# 3_IO.net
KiCad netlist of a schematic drawn in Altium Designer
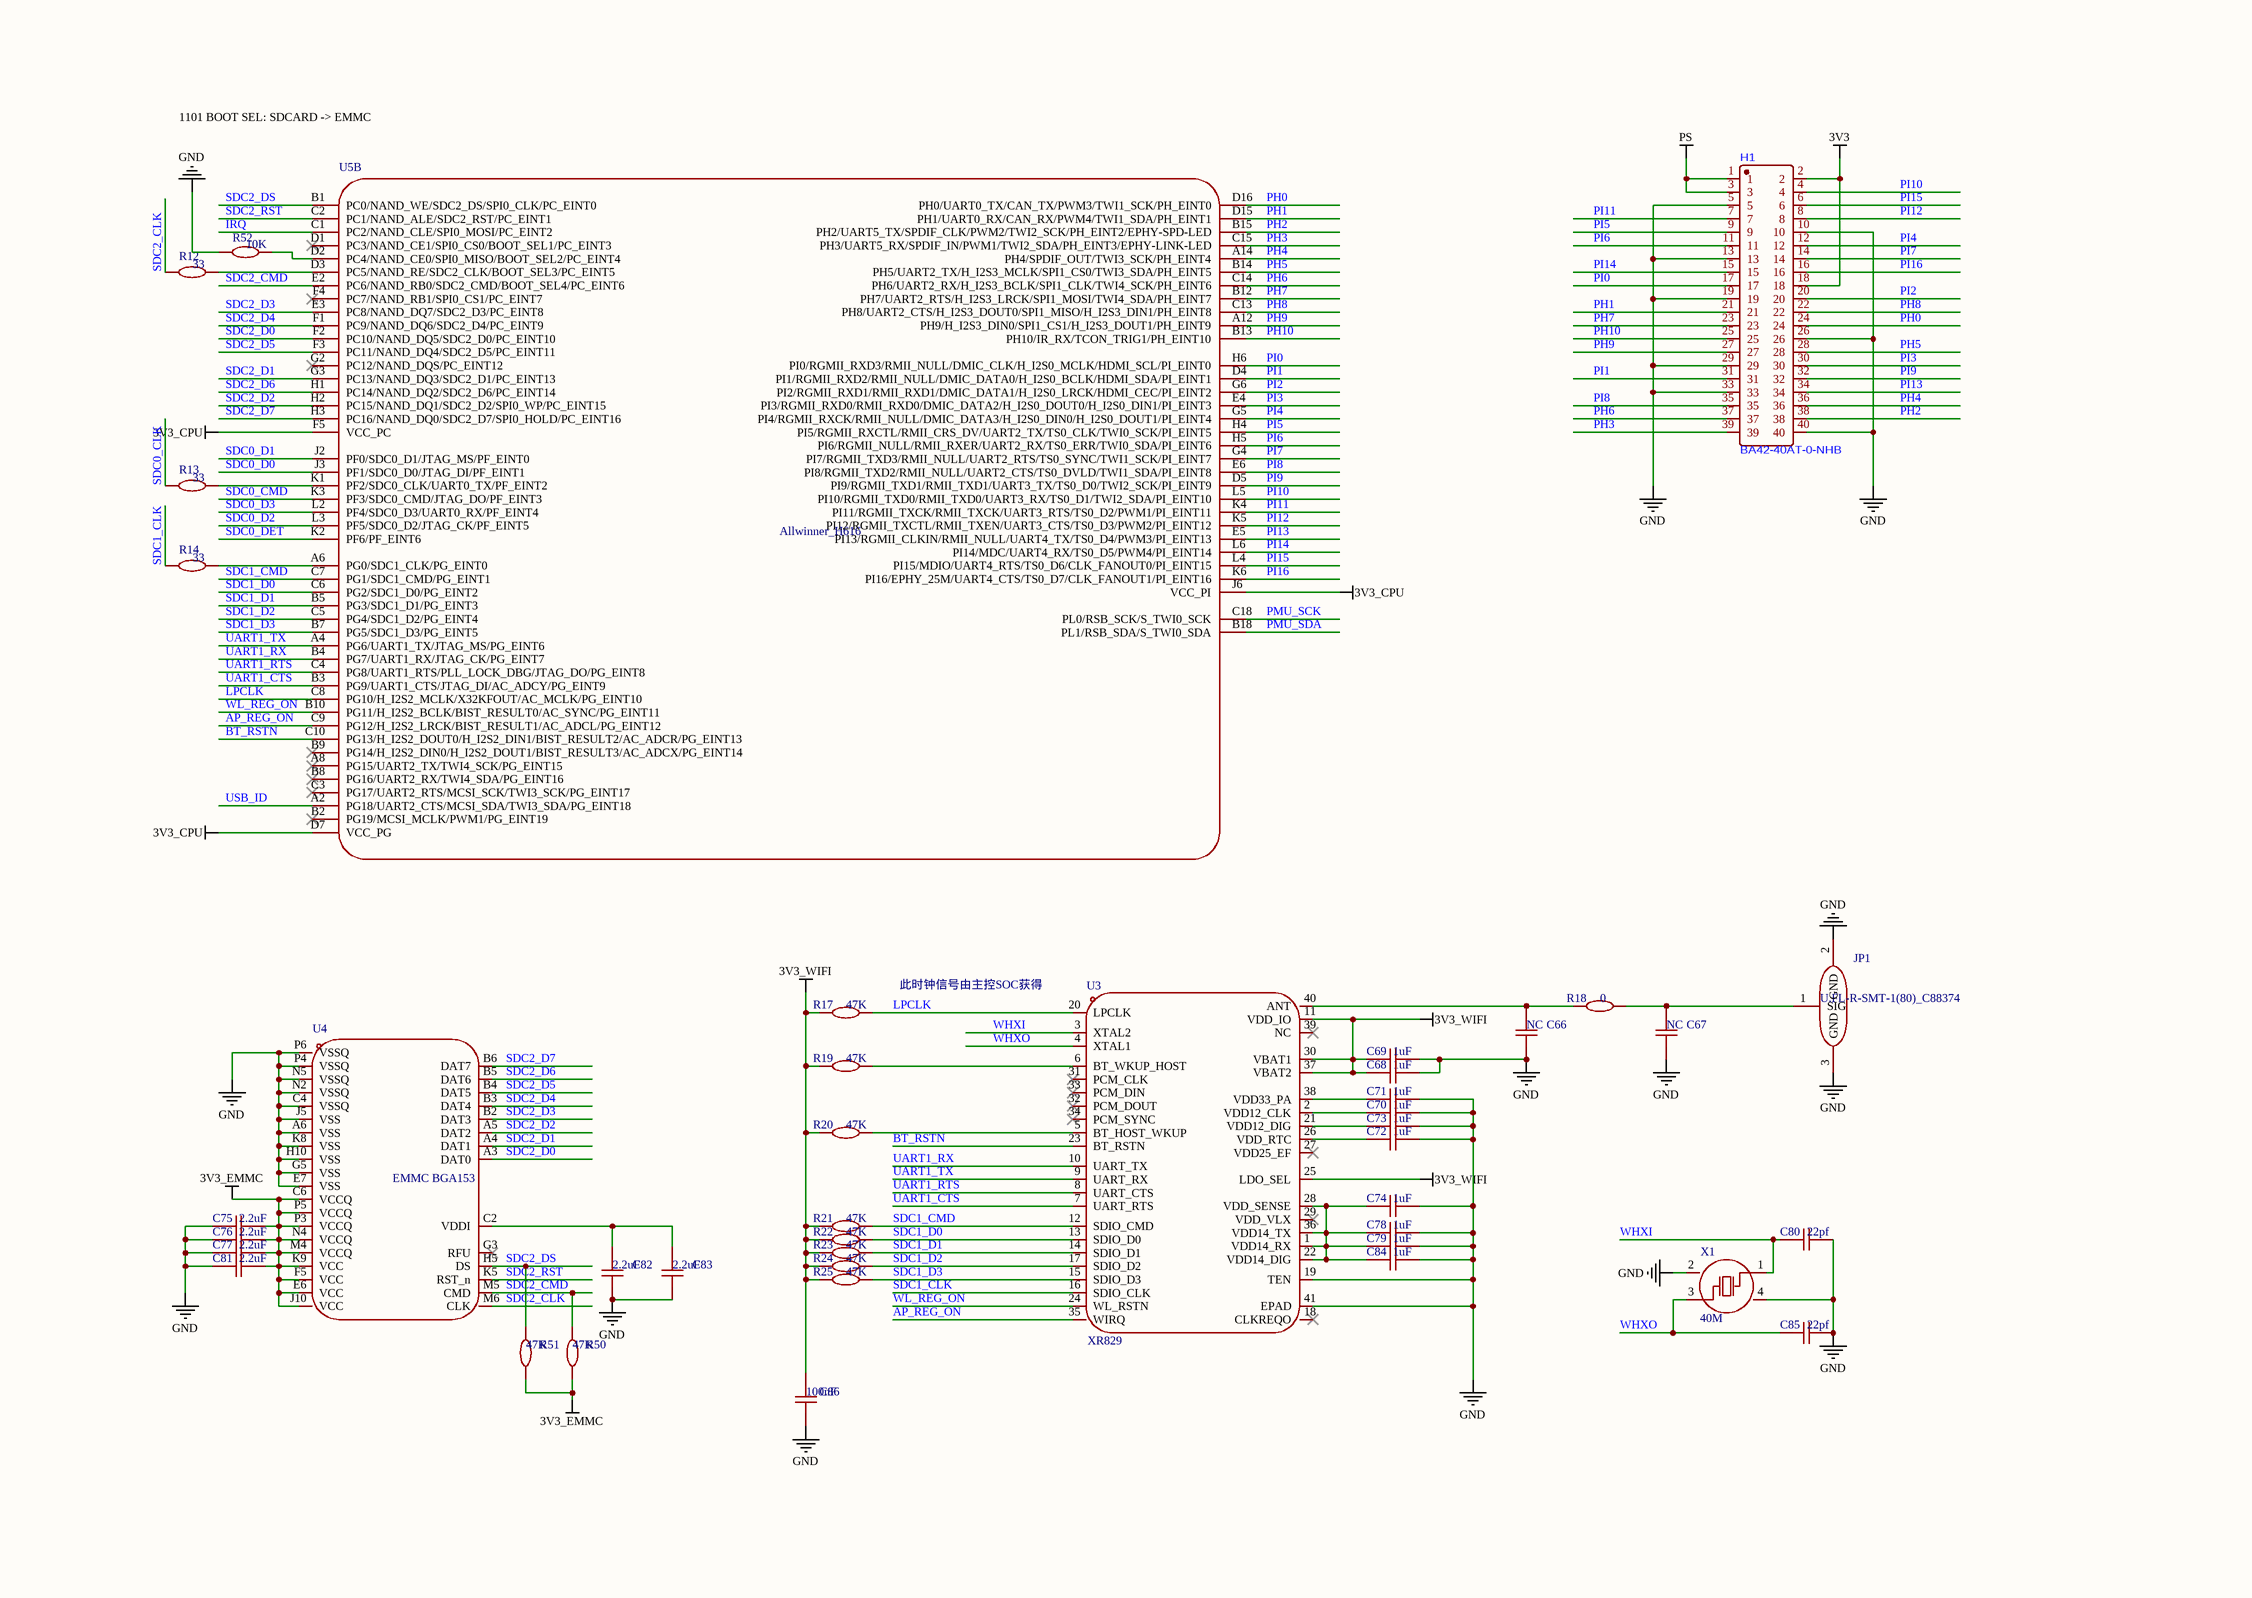
[diagram p0: 3_IO.schdoc]

(export (version "E")
  (design (tool "Eeschema 10.0.6"))
  (components
    (comp (ref "C66") (value "NC") (footprint "PCB:C0402") (libsource (lib "PCB_Project") (part "CAP_0402")))
    (comp (ref "C67") (value "NC") (footprint "PCB:C0402") (libsource (lib "PCB_Project") (part "CAP_0402")))
    (comp (ref "C68") (value "1uF") (footprint "PCB:C0402") (libsource (lib "PCB_Project") (part "CAP_0402")))
    (comp (ref "C69") (value "1uF") (footprint "PCB:C0402") (libsource (lib "PCB_Project") (part "CAP_0402")))
    (comp (ref "C70") (value "1uF") (footprint "PCB:C0402") (libsource (lib "PCB_Project") (part "CAP_0402")))
    (comp (ref "C71") (value "1uF") (footprint "PCB:C0402") (libsource (lib "PCB_Project") (part "CAP_0402")))
    (comp (ref "C72") (value "1uF") (footprint "PCB:C0402") (libsource (lib "PCB_Project") (part "CAP_0402")))
    (comp (ref "C73") (value "1uF") (footprint "PCB:C0402") (libsource (lib "PCB_Project") (part "CAP_0402")))
    (comp (ref "C74") (value "1uF") (footprint "PCB:C0402") (libsource (lib "PCB_Project") (part "CAP_0402")))
    (comp (ref "C75")
      (value "2.2uF")
      (footprint "PCB:C0402")
      (libsource (lib "PCB_Project") (part "CAP_0402"))
    )
    (comp (ref "C76")
      (value "2.2uF")
      (footprint "PCB:C0402")
      (libsource (lib "PCB_Project") (part "CAP_0402"))
    )
    (comp (ref "C77")
      (value "2.2uF")
      (footprint "PCB:C0402")
      (libsource (lib "PCB_Project") (part "CAP_0402"))
    )
    (comp (ref "C78") (value "1uF") (footprint "PCB:C0402") (libsource (lib "PCB_Project") (part "CAP_0402")))
    (comp (ref "C79") (value "1uF") (footprint "PCB:C0402") (libsource (lib "PCB_Project") (part "CAP_0402")))
    (comp (ref "C80")
      (value "22pf")
      (footprint "PCB:C0402")
      (libsource (lib "PCB_Project") (part "CAP_0402"))
    )
    (comp (ref "C81")
      (value "2.2uF")
      (footprint "PCB:C0402")
      (libsource (lib "PCB_Project") (part "CAP_0402"))
    )
    (comp (ref "C82")
      (value "2.2uF")
      (footprint "PCB:C0402")
      (libsource (lib "PCB_Project") (part "CAP_0402"))
    )
    (comp (ref "C83")
      (value "2.2uF")
      (footprint "PCB:C0402")
      (libsource (lib "PCB_Project") (part "CAP_0402"))
    )
    (comp (ref "C84") (value "1uF") (footprint "PCB:C0402") (libsource (lib "PCB_Project") (part "CAP_0402")))
    (comp (ref "C85")
      (value "22pf")
      (footprint "PCB:C0402")
      (libsource (lib "PCB_Project") (part "CAP_0402"))
    )
    (comp (ref "C86")
      (value "100nF")
      (footprint "PCB:c0402-nsk_1")
      (libsource (lib "PCB_Project") (part "FN15X104K250PNG"))
    )
    (comp (ref "H1")
      (value "BA42-40AT-0-NHB")
      (footprint "PCB:CONN-SMD_40P-P0.80_10144517-042802LF")
      (libsource (lib "PCB_Project") (part "BA42-40AT-0-NHB"))
    )
    (comp (ref "JP1")
      (value "U.FL-R-SMT-1(80)_C88374")
      (footprint "PCB:RF-SMD_FRF05002-JSS103M")
      (libsource (lib "PCB_Project") (part "U.FL-R-SMT-1(80)_C88374"))
    )
    (comp (ref "R12")
      (value "33")
      (footprint "PCB:R0402-NSK_2")
      (libsource (lib "PCB_Project") (part "Res_0402"))
    )
    (comp (ref "R13")
      (value "33")
      (footprint "PCB:R0402-NSK_2")
      (libsource (lib "PCB_Project") (part "Res_0402"))
    )
    (comp (ref "R14")
      (value "33")
      (footprint "PCB:R0402-NSK_2")
      (libsource (lib "PCB_Project") (part "Res_0402"))
    )
    (comp (ref "R17")
      (value "47K")
      (footprint "PCB:R0402-NSK_2")
      (libsource (lib "PCB_Project") (part "Res_0402"))
    )
    (comp (ref "R18")
      (value "0")
      (footprint "PCB:R0402-NSK_2")
      (libsource (lib "PCB_Project") (part "Res_0402"))
    )
    (comp (ref "R19")
      (value "47K")
      (footprint "PCB:R0402-NSK_2")
      (libsource (lib "PCB_Project") (part "Res_0402"))
    )
    (comp (ref "R20")
      (value "47K")
      (footprint "PCB:R0402-NSK_2")
      (libsource (lib "PCB_Project") (part "Res_0402"))
    )
    (comp (ref "R21")
      (value "47K")
      (footprint "PCB:R0402-NSK_2")
      (libsource (lib "PCB_Project") (part "Res_0402"))
    )
    (comp (ref "R22")
      (value "47K")
      (footprint "PCB:R0402-NSK_2")
      (libsource (lib "PCB_Project") (part "Res_0402"))
    )
    (comp (ref "R23")
      (value "47K")
      (footprint "PCB:R0402-NSK_2")
      (libsource (lib "PCB_Project") (part "Res_0402"))
    )
    (comp (ref "R24")
      (value "47K")
      (footprint "PCB:R0402-NSK_2")
      (libsource (lib "PCB_Project") (part "Res_0402"))
    )
    (comp (ref "R25")
      (value "47K")
      (footprint "PCB:R0402-NSK_2")
      (libsource (lib "PCB_Project") (part "Res_0402"))
    )
    (comp (ref "R50")
      (value "47K")
      (footprint "PCB:R0402-NSK_2")
      (libsource (lib "PCB_Project") (part "Res_0402"))
    )
    (comp (ref "R51")
      (value "47K")
      (footprint "PCB:R0402-NSK_2")
      (libsource (lib "PCB_Project") (part "Res_0402"))
    )
    (comp (ref "R52")
      (value "10K")
      (footprint "PCB:R0402-NSK_2")
      (libsource (lib "PCB_Project") (part "Res_0402"))
    )
    (comp (ref "U3")
      (value "XR829")
      (footprint "PCB:QFN-40_L5.0-W5.0-P0.40-BL-EP3.4")
      (libsource (lib "PCB_Project") (part "XR829"))
    )
    (comp (ref "U4")
      (value "EMMC BGA153")
      (footprint "PCB:FBGA-153_L13.0-W11.5")
      (libsource (lib "PCB_Project") (part "EMMC BGA153"))
    )
    (comp (ref "U5")
      (value "Allwinner_H616")
      (footprint "PCB:BGA284P65B1200_1400H125")
      (libsource (lib "PCB_Project") (part "Allwinner_H616"))
    )
    (comp (ref "X1")
      (value "40M")
      (footprint "PCB:OSC-SMD_4P-L2.0-W1.6-BL")
      (libsource (lib "PCB_Project") (part "SX32Y024000BC1T"))
    )
  )
  (nets
    (net (code "1") (name "/AP_REG_ON") (class "Default")
      (node (ref "U3") (pin "35") (pinfunction "WIRQ_35") (pintype "passive"))
      (node (ref "U5") (pin "C9") (pinfunction "PG12/H_I2S2_LRCK/BIST_RESULT1/AC_ADCL/PG_EINT12_C9") (pintype "passive"))
    )
    (net (code "2") (name "/BT_RSTN") (class "Default")
      (node (ref "U3") (pin "23") (pinfunction "BT_RSTN_23") (pintype "passive"))
      (node (ref "U5") (pin "C10") (pinfunction "PG13/H_I2S2_DOUT0/H_I2S2_DIN1/BIST_RESULT2/AC_ADCR/PG_EINT13_C10") (pintype "passive"))
    )
    (net (code "3") (name "/IRQ") (class "Default")
      (node (ref "U5") (pin "C1") (pinfunction "PC2/NAND_CLE/SPI0_MOSI/PC_EINT2_C1") (pintype "passive"))
    )
    (net (code "4") (name "/LPCLK") (class "Default")
      (node (ref "R17") (pin "2") (pinfunction "2_2") (pintype "passive"))
      (node (ref "U3") (pin "20") (pinfunction "LPCLK_20") (pintype "passive"))
      (node (ref "U5") (pin "C8") (pinfunction "PG10/H_I2S2_MCLK/X32KFOUT/AC_MCLK/PG_EINT10_C8") (pintype "passive"))
    )
    (net (code "5") (name "/PH0") (class "Default")
      (node (ref "H1") (pin "24") (pinfunction "24_24") (pintype "passive"))
      (node (ref "U5") (pin "D16") (pinfunction "PH0/UART0_TX/CAN_TX/PWM3/TWI1_SCK/PH_EINT0_D16") (pintype "passive"))
    )
    (net (code "6") (name "/PH1") (class "Default")
      (node (ref "H1") (pin "21") (pinfunction "21_21") (pintype "passive"))
      (node (ref "U5") (pin "D15") (pinfunction "PH1/UART0_RX/CAN_RX/PWM4/TWI1_SDA/PH_EINT1_D15") (pintype "passive"))
    )
    (net (code "7") (name "/PH2") (class "Default")
      (node (ref "H1") (pin "38") (pinfunction "38_38") (pintype "passive"))
      (node (ref "U5") (pin "B15") (pinfunction "PH2/UART5_TX/SPDIF_CLK/PWM2/TWI2_SCK/PH_EINT2/EPHY-SPD-LED_B15") (pintype "passive"))
    )
    (net (code "8") (name "/PH3") (class "Default")
      (node (ref "H1") (pin "39") (pinfunction "39_39") (pintype "passive"))
      (node (ref "U5") (pin "C15") (pinfunction "PH3/UART5_RX/SPDIF_IN/PWM1/TWI2_SDA/PH_EINT3/EPHY-LINK-LED_C15") (pintype "passive"))
    )
    (net (code "9") (name "/PH4") (class "Default")
      (node (ref "H1") (pin "36") (pinfunction "36_36") (pintype "passive"))
      (node (ref "U5") (pin "A14") (pinfunction "PH4/SPDIF_OUT/TWI3_SCK/PH_EINT4_A14") (pintype "passive"))
    )
    (net (code "10") (name "/PH5") (class "Default")
      (node (ref "H1") (pin "28") (pinfunction "28_28") (pintype "passive"))
      (node (ref "U5") (pin "B14") (pinfunction "PH5/UART2_TX/H_I2S3_MCLK/SPI1_CS0/TWI3_SDA/PH_EINT5_B14") (pintype "passive"))
    )
    (net (code "11") (name "/PH6") (class "Default")
      (node (ref "H1") (pin "37") (pinfunction "37_37") (pintype "passive"))
      (node (ref "U5") (pin "C14") (pinfunction "PH6/UART2_RX/H_I2S3_BCLK/SPI1_CLK/TWI4_SCK/PH_EINT6_C14") (pintype "passive"))
    )
    (net (code "12") (name "/PH7") (class "Default")
      (node (ref "H1") (pin "23") (pinfunction "23_23") (pintype "passive"))
      (node (ref "U5") (pin "B12") (pinfunction "PH7/UART2_RTS/H_I2S3_LRCK/SPI1_MOSI/TWI4_SDA/PH_EINT7_B12") (pintype "passive"))
    )
    (net (code "13") (name "/PH8") (class "Default")
      (node (ref "H1") (pin "22") (pinfunction "22_22") (pintype "passive"))
      (node (ref "U5") (pin "C13") (pinfunction "PH8/UART2_CTS/H_I2S3_DOUT0/SPI1_MISO/H_I2S3_DIN1/PH_EINT8_C13") (pintype "passive"))
    )
    (net (code "14") (name "/PH9") (class "Default")
      (node (ref "H1") (pin "27") (pinfunction "27_27") (pintype "passive"))
      (node (ref "U5") (pin "A12") (pinfunction "PH9/H_I2S3_DIN0/SPI1_CS1/H_I2S3_DOUT1/PH_EINT9_A12") (pintype "passive"))
    )
    (net (code "15") (name "/PH10") (class "Default")
      (node (ref "H1") (pin "25") (pinfunction "25_25") (pintype "passive"))
      (node (ref "U5") (pin "B13") (pinfunction "PH10/IR_RX/TCON_TRIG1/PH_EINT10_B13") (pintype "passive"))
    )
    (net (code "16") (name "/PI0") (class "Default")
      (node (ref "H1") (pin "17") (pinfunction "17_17") (pintype "passive"))
      (node (ref "U5") (pin "H6") (pinfunction "PI0/RGMII_RXD3/RMII_NULL/DMIC_CLK/H_I2S0_MCLK/HDMI_SCL/PI_EINT0_H6") (pintype "passive"))
    )
    (net (code "17") (name "/PI1") (class "Default")
      (node (ref "H1") (pin "31") (pinfunction "31_31") (pintype "passive"))
      (node (ref "U5") (pin "D4") (pinfunction "PI1/RGMII_RXD2/RMII_NULL/DMIC_DATA0/H_I2S0_BCLK/HDMI_SDA/PI_EINT1_D4") (pintype "passive"))
    )
    (net (code "18") (name "/PI2") (class "Default")
      (node (ref "H1") (pin "20") (pinfunction "20_20") (pintype "passive"))
      (node (ref "U5") (pin "G6") (pinfunction "PI2/RGMII_RXD1/RMII_RXD1/DMIC_DATA1/H_I2S0_LRCK/HDMI_CEC/PI_EINT2_G6") (pintype "passive"))
    )
    (net (code "19") (name "/PI3") (class "Default")
      (node (ref "H1") (pin "30") (pinfunction "30_30") (pintype "passive"))
      (node (ref "U5") (pin "E4") (pinfunction "PI3/RGMII_RXD0/RMII_RXD0/DMIC_DATA2/H_I2S0_DOUT0/H_I2S0_DIN1/PI_EINT3_E4") (pintype "passive"))
    )
    (net (code "20") (name "/PI4") (class "Default")
      (node (ref "H1") (pin "12") (pinfunction "12_12") (pintype "passive"))
      (node (ref "U5") (pin "G5") (pinfunction "PI4/RGMII_RXCK/RMII_NULL/DMIC_DATA3/H_I2S0_DIN0/H_I2S0_DOUT1/PI_EINT4_G5") (pintype "passive"))
    )
    (net (code "21") (name "/PI5") (class "Default")
      (node (ref "H1") (pin "9") (pinfunction "9_9") (pintype "passive"))
      (node (ref "U5") (pin "H4") (pinfunction "PI5/RGMII_RXCTL/RMII_CRS_DV/UART2_TX/TS0_CLK/TWI0_SCK/PI_EINT5_H4") (pintype "passive"))
    )
    (net (code "22") (name "/PI6") (class "Default")
      (node (ref "H1") (pin "11") (pinfunction "11_11") (pintype "passive"))
      (node (ref "U5") (pin "H5") (pinfunction "PI6/RGMII_NULL/RMII_RXER/UART2_RX/TS0_ERR/TWI0_SDA/PI_EINT6_H5") (pintype "passive"))
    )
    (net (code "23") (name "/PI7") (class "Default")
      (node (ref "H1") (pin "14") (pinfunction "14_14") (pintype "passive"))
      (node (ref "U5") (pin "G4") (pinfunction "PI7/RGMII_TXD3/RMII_NULL/UART2_RTS/TS0_SYNC/TWI1_SCK/PI_EINT7_G4") (pintype "passive"))
    )
    (net (code "24") (name "/PI8") (class "Default")
      (node (ref "H1") (pin "35") (pinfunction "35_35") (pintype "passive"))
      (node (ref "U5") (pin "E6") (pinfunction "PI8/RGMII_TXD2/RMII_NULL/UART2_CTS/TS0_DVLD/TWI1_SDA/PI_EINT8_E6") (pintype "passive"))
    )
    (net (code "25") (name "/PI9") (class "Default")
      (node (ref "H1") (pin "32") (pinfunction "32_32") (pintype "passive"))
      (node (ref "U5") (pin "D5") (pinfunction "PI9/RGMII_TXD1/RMII_TXD1/UART3_TX/TS0_D0/TWI2_SCK/PI_EINT9_D5") (pintype "passive"))
    )
    (net (code "26") (name "/PI10") (class "Default")
      (node (ref "H1") (pin "4") (pinfunction "4_4") (pintype "passive"))
      (node (ref "U5") (pin "L5") (pinfunction "PI10/RGMII_TXD0/RMII_TXD0/UART3_RX/TS0_D1/TWI2_SDA/PI_EINT10_L5") (pintype "passive"))
    )
    (net (code "27") (name "/PI11") (class "Default")
      (node (ref "H1") (pin "7") (pinfunction "7_7") (pintype "passive"))
      (node (ref "U5") (pin "K4") (pinfunction "PI11/RGMII_TXCK/RMII_TXCK/UART3_RTS/TS0_D2/PWM1/PI_EINT11_K4") (pintype "passive"))
    )
    (net (code "28") (name "/PI12") (class "Default")
      (node (ref "H1") (pin "8") (pinfunction "8_8") (pintype "passive"))
      (node (ref "U5") (pin "K5") (pinfunction "PI12/RGMII_TXCTL/RMII_TXEN/UART3_CTS/TS0_D3/PWM2/PI_EINT12_K5") (pintype "passive"))
    )
    (net (code "29") (name "/PI13") (class "Default")
      (node (ref "H1") (pin "34") (pinfunction "34_34") (pintype "passive"))
      (node (ref "U5") (pin "E5") (pinfunction "PI13/RGMII_CLKIN/RMII_NULL/UART4_TX/TS0_D4/PWM3/PI_EINT13_E5") (pintype "passive"))
    )
    (net (code "30") (name "/PI14") (class "Default")
      (node (ref "H1") (pin "15") (pinfunction "15_15") (pintype "passive"))
      (node (ref "U5") (pin "L6") (pinfunction "PI14/MDC/UART4_RX/TS0_D5/PWM4/PI_EINT14_L6") (pintype "passive"))
    )
    (net (code "31") (name "/PI15") (class "Default")
      (node (ref "H1") (pin "6") (pinfunction "6_6") (pintype "passive"))
      (node (ref "U5") (pin "L4") (pinfunction "PI15/MDIO/UART4_RTS/TS0_D6/CLK_FANOUT0/PI_EINT15_L4") (pintype "passive"))
    )
    (net (code "32") (name "/PI16") (class "Default")
      (node (ref "H1") (pin "16") (pinfunction "16_16") (pintype "passive"))
      (node (ref "U5") (pin "K6") (pinfunction "PI16/EPHY_25M/UART4_CTS/TS0_D7/CLK_FANOUT1/PI_EINT16_K6") (pintype "passive"))
    )
    (net (code "33") (name "/PMU_SCK") (class "Default")
      (node (ref "U5") (pin "C18") (pinfunction "PL0/RSB_SCK/S_TWI0_SCK_C18") (pintype "passive"))
    )
    (net (code "34") (name "/PMU_SDA") (class "Default")
      (node (ref "U5") (pin "B18") (pinfunction "PL1/RSB_SDA/S_TWI0_SDA_B18") (pintype "passive"))
    )
    (net (code "35") (name "/SDC0_CLK") (class "Default")
      (node (ref "R13") (pin "1") (pinfunction "1_1") (pintype "passive"))
    )
    (net (code "36") (name "/SDC0_CMD") (class "Default")
      (node (ref "U5") (pin "K3") (pinfunction "PF3/SDC0_CMD/JTAG_DO/PF_EINT3_K3") (pintype "passive"))
    )
    (net (code "37") (name "/SDC0_D0") (class "Default")
      (node (ref "U5") (pin "J3") (pinfunction "PF1/SDC0_D0/JTAG_DI/PF_EINT1_J3") (pintype "passive"))
    )
    (net (code "38") (name "/SDC0_D1") (class "Default")
      (node (ref "U5") (pin "J2") (pinfunction "PF0/SDC0_D1/JTAG_MS/PF_EINT0_J2") (pintype "passive"))
    )
    (net (code "39") (name "/SDC0_D2") (class "Default")
      (node (ref "U5") (pin "L3") (pinfunction "PF5/SDC0_D2/JTAG_CK/PF_EINT5_L3") (pintype "passive"))
    )
    (net (code "40") (name "/SDC0_D3") (class "Default")
      (node (ref "U5") (pin "L2") (pinfunction "PF4/SDC0_D3/UART0_RX/PF_EINT4_L2") (pintype "passive"))
    )
    (net (code "41") (name "/SDC0_DET") (class "Default")
      (node (ref "U5") (pin "K2") (pinfunction "PF6/PF_EINT6_K2") (pintype "passive"))
    )
    (net (code "42") (name "/SDC1_CLK") (class "Default")
      (node (ref "R14") (pin "1") (pinfunction "1_1") (pintype "passive"))
      (node (ref "U3") (pin "16") (pinfunction "SDIO_CLK_16") (pintype "passive"))
    )
    (net (code "43") (name "/SDC1_CMD") (class "Default")
      (node (ref "R21") (pin "2") (pinfunction "2_2") (pintype "passive"))
      (node (ref "U3") (pin "12") (pinfunction "SDIO_CMD_12") (pintype "passive"))
      (node (ref "U5") (pin "C7") (pinfunction "PG1/SDC1_CMD/PG_EINT1_C7") (pintype "passive"))
    )
    (net (code "44") (name "/SDC1_D0") (class "Default")
      (node (ref "R22") (pin "2") (pinfunction "2_2") (pintype "passive"))
      (node (ref "U3") (pin "13") (pinfunction "SDIO_D0_13") (pintype "passive"))
      (node (ref "U5") (pin "C6") (pinfunction "PG2/SDC1_D0/PG_EINT2_C6") (pintype "passive"))
    )
    (net (code "45") (name "/SDC1_D1") (class "Default")
      (node (ref "R23") (pin "2") (pinfunction "2_2") (pintype "passive"))
      (node (ref "U3") (pin "14") (pinfunction "SDIO_D1_14") (pintype "passive"))
      (node (ref "U5") (pin "B5") (pinfunction "PG3/SDC1_D1/PG_EINT3_B5") (pintype "passive"))
    )
    (net (code "46") (name "/SDC1_D2") (class "Default")
      (node (ref "R24") (pin "2") (pinfunction "2_2") (pintype "passive"))
      (node (ref "U3") (pin "17") (pinfunction "SDIO_D2_17") (pintype "passive"))
      (node (ref "U5") (pin "C5") (pinfunction "PG4/SDC1_D2/PG_EINT4_C5") (pintype "passive"))
    )
    (net (code "47") (name "/SDC1_D3") (class "Default")
      (node (ref "R25") (pin "2") (pinfunction "2_2") (pintype "passive"))
      (node (ref "U3") (pin "15") (pinfunction "SDIO_D3_15") (pintype "passive"))
      (node (ref "U5") (pin "B7") (pinfunction "PG5/SDC1_D3/PG_EINT5_B7") (pintype "passive"))
    )
    (net (code "48") (name "/SDC2_CLK") (class "Default")
      (node (ref "R12") (pin "1") (pinfunction "1_1") (pintype "passive"))
      (node (ref "U4") (pin "M6") (pinfunction "CLK_M6") (pintype "passive"))
    )
    (net (code "49") (name "/SDC2_CMD") (class "Default")
      (node (ref "R50") (pin "2") (pinfunction "2_2") (pintype "passive"))
      (node (ref "U4") (pin "M5") (pinfunction "CMD_M5") (pintype "passive"))
      (node (ref "U5") (pin "E2") (pinfunction "PC6/NAND_RB0/SDC2_CMD/BOOT_SEL4/PC_EINT6_E2") (pintype "passive"))
    )
    (net (code "50") (name "/SDC2_D0") (class "Default")
      (node (ref "U4") (pin "A3") (pinfunction "DAT0_A3") (pintype "passive"))
      (node (ref "U5") (pin "F2") (pinfunction "PC10/NAND_DQ5/SDC2_D0/PC_EINT10_F2") (pintype "passive"))
    )
    (net (code "51") (name "/SDC2_D1") (class "Default")
      (node (ref "U4") (pin "A4") (pinfunction "DAT1_A4") (pintype "passive"))
      (node (ref "U5") (pin "G3") (pinfunction "PC13/NAND_DQ3/SDC2_D1/PC_EINT13_G3") (pintype "passive"))
    )
    (net (code "52") (name "/SDC2_D2") (class "Default")
      (node (ref "U4") (pin "A5") (pinfunction "DAT2_A5") (pintype "passive"))
      (node (ref "U5") (pin "H2") (pinfunction "PC15/NAND_DQ1/SDC2_D2/SPI0_WP/PC_EINT15_H2") (pintype "passive"))
    )
    (net (code "53") (name "/SDC2_D3") (class "Default")
      (node (ref "U4") (pin "B2") (pinfunction "DAT3_B2") (pintype "passive"))
      (node (ref "U5") (pin "E3") (pinfunction "PC8/NAND_DQ7/SDC2_D3/PC_EINT8_E3") (pintype "passive"))
    )
    (net (code "54") (name "/SDC2_D4") (class "Default")
      (node (ref "U4") (pin "B3") (pinfunction "DAT4_B3") (pintype "passive"))
      (node (ref "U5") (pin "F1") (pinfunction "PC9/NAND_DQ6/SDC2_D4/PC_EINT9_F1") (pintype "passive"))
    )
    (net (code "55") (name "/SDC2_D5") (class "Default")
      (node (ref "U4") (pin "B4") (pinfunction "DAT5_B4") (pintype "passive"))
      (node (ref "U5") (pin "F3") (pinfunction "PC11/NAND_DQ4/SDC2_D5/PC_EINT11_F3") (pintype "passive"))
    )
    (net (code "56") (name "/SDC2_D6") (class "Default")
      (node (ref "U4") (pin "B5") (pinfunction "DAT6_B5") (pintype "passive"))
      (node (ref "U5") (pin "H1") (pinfunction "PC14/NAND_DQ2/SDC2_D6/PC_EINT14_H1") (pintype "passive"))
    )
    (net (code "57") (name "/SDC2_D7") (class "Default")
      (node (ref "U4") (pin "B6") (pinfunction "DAT7_B6") (pintype "passive"))
      (node (ref "U5") (pin "H3") (pinfunction "PC16/NAND_DQ0/SDC2_D7/SPI0_HOLD/PC_EINT16_H3") (pintype "passive"))
    )
    (net (code "58") (name "/SDC2_DS") (class "Default")
      (node (ref "R51") (pin "2") (pinfunction "2_2") (pintype "passive"))
      (node (ref "U4") (pin "H5") (pinfunction "DS_H5") (pintype "passive"))
      (node (ref "U5") (pin "B1") (pinfunction "PC0/NAND_WE/SDC2_DS/SPI0_CLK/PC_EINT0_B1") (pintype "passive"))
    )
    (net (code "59") (name "/SDC2_RST") (class "Default")
      (node (ref "U4") (pin "K5") (pinfunction "RST_n_K5") (pintype "passive"))
      (node (ref "U5") (pin "C2") (pinfunction "PC1/NAND_ALE/SDC2_RST/PC_EINT1_C2") (pintype "passive"))
    )
    (net (code "60") (name "/UART1_CTS") (class "Default")
      (node (ref "U3") (pin "7") (pinfunction "UART_RTS_7") (pintype "passive"))
      (node (ref "U5") (pin "B3") (pinfunction "PG9/UART1_CTS/JTAG_DI/AC_ADCY/PG_EINT9_B3") (pintype "passive"))
    )
    (net (code "61") (name "/UART1_RTS") (class "Default")
      (node (ref "U3") (pin "8") (pinfunction "UART_CTS_8") (pintype "passive"))
      (node (ref "U5") (pin "C4") (pinfunction "PG8/UART1_RTS/PLL_LOCK_DBG/JTAG_DO/PG_EINT8_C4") (pintype "passive"))
    )
    (net (code "62") (name "/UART1_RX") (class "Default")
      (node (ref "U3") (pin "10") (pinfunction "UART_TX_10") (pintype "passive"))
      (node (ref "U5") (pin "B4") (pinfunction "PG7/UART1_RX/JTAG_CK/PG_EINT7_B4") (pintype "passive"))
    )
    (net (code "63") (name "/UART1_TX") (class "Default")
      (node (ref "U3") (pin "9") (pinfunction "UART_RX_9") (pintype "passive"))
      (node (ref "U5") (pin "A4") (pinfunction "PG6/UART1_TX/JTAG_MS/PG_EINT6_A4") (pintype "passive"))
    )
    (net (code "64") (name "/USB_ID") (class "Default")
      (node (ref "U5") (pin "A2") (pinfunction "PG18/UART2_CTS/MCSI_SDA/TWI3_SDA/PG_EINT18_A2") (pintype "passive"))
    )
    (net (code "65") (name "/WHXI") (class "Default")
      (node (ref "C80") (pin "1") (pinfunction "1_1") (pintype "passive"))
      (node (ref "U3") (pin "3") (pinfunction "XTAL2_3") (pintype "passive"))
      (node (ref "X1") (pin "1") (pinfunction "OSC1_1") (pintype "passive"))
    )
    (net (code "66") (name "/WHXO") (class "Default")
      (node (ref "C85") (pin "1") (pinfunction "1_1") (pintype "passive"))
      (node (ref "U3") (pin "4") (pinfunction "XTAL1_4") (pintype "passive"))
      (node (ref "X1") (pin "3") (pinfunction "OSC2_3") (pintype "passive"))
    )
    (net (code "67") (name "/WL_REG_ON") (class "Default")
      (node (ref "U3") (pin "24") (pinfunction "WL_RSTN_24") (pintype "passive"))
      (node (ref "U5") (pin "B10") (pinfunction "PG11/H_I2S2_BCLK/BIST_RESULT0/AC_SYNC/PG_EINT11_B10") (pintype "passive"))
    )
    (net (code "68") (name "3V3") (class "Default")
      (node (ref "H1") (pin "18") (pinfunction "18_18") (pintype "passive"))
      (node (ref "H1") (pin "2") (pinfunction "2_2") (pintype "passive"))
    )
    (net (code "69") (name "3V3_CPU") (class "Default")
      (node (ref "U5") (pin "D7") (pinfunction "VCC_PG_D7") (pintype "passive"))
      (node (ref "U5") (pin "F5") (pinfunction "VCC_PC_F5") (pintype "passive"))
      (node (ref "U5") (pin "J6") (pinfunction "VCC_PI_J6") (pintype "passive"))
    )
    (net (code "70") (name "3V3_EMMC") (class "Default")
      (node (ref "C75") (pin "2") (pinfunction "2_2") (pintype "passive"))
      (node (ref "C76") (pin "2") (pinfunction "2_2") (pintype "passive"))
      (node (ref "C77") (pin "2") (pinfunction "2_2") (pintype "passive"))
      (node (ref "C81") (pin "2") (pinfunction "2_2") (pintype "passive"))
      (node (ref "R50") (pin "1") (pinfunction "1_1") (pintype "passive"))
      (node (ref "R51") (pin "1") (pinfunction "1_1") (pintype "passive"))
      (node (ref "U4") (pin "C6") (pinfunction "VCCQ_C6") (pintype "passive"))
      (node (ref "U4") (pin "E6") (pinfunction "VCC_E6") (pintype "passive"))
      (node (ref "U4") (pin "F5") (pinfunction "VCC_F5") (pintype "passive"))
      (node (ref "U4") (pin "J10") (pinfunction "VCC_J10") (pintype "passive"))
      (node (ref "U4") (pin "K9") (pinfunction "VCC_K9") (pintype "passive"))
      (node (ref "U4") (pin "M4") (pinfunction "VCCQ_M4") (pintype "passive"))
      (node (ref "U4") (pin "N4") (pinfunction "VCCQ_N4") (pintype "passive"))
      (node (ref "U4") (pin "P3") (pinfunction "VCCQ_P3") (pintype "passive"))
      (node (ref "U4") (pin "P5") (pinfunction "VCCQ_P5") (pintype "passive"))
    )
    (net (code "71") (name "3V3_WIFI") (class "Default")
      (node (ref "C68") (pin "1") (pinfunction "1_1") (pintype "passive"))
      (node (ref "C69") (pin "1") (pinfunction "1_1") (pintype "passive"))
      (node (ref "C86") (pin "2") (pinfunction "2_2") (pintype "passive"))
      (node (ref "R17") (pin "1") (pinfunction "1_1") (pintype "passive"))
      (node (ref "R19") (pin "1") (pinfunction "1_1") (pintype "passive"))
      (node (ref "R20") (pin "1") (pinfunction "1_1") (pintype "passive"))
      (node (ref "R21") (pin "1") (pinfunction "1_1") (pintype "passive"))
      (node (ref "R22") (pin "1") (pinfunction "1_1") (pintype "passive"))
      (node (ref "R23") (pin "1") (pinfunction "1_1") (pintype "passive"))
      (node (ref "R24") (pin "1") (pinfunction "1_1") (pintype "passive"))
      (node (ref "R25") (pin "1") (pinfunction "1_1") (pintype "passive"))
      (node (ref "U3") (pin "11") (pinfunction "VDD_IO_11") (pintype "passive"))
      (node (ref "U3") (pin "25") (pinfunction "LDO_SEL_25") (pintype "passive"))
      (node (ref "U3") (pin "30") (pinfunction "VBAT1_30") (pintype "passive"))
      (node (ref "U3") (pin "37") (pinfunction "VBAT2_37") (pintype "passive"))
    )
    (net (code "72") (name "GND") (class "Default")
      (node (ref "C66") (pin "1") (pinfunction "1_1") (pintype "passive"))
      (node (ref "C67") (pin "1") (pinfunction "1_1") (pintype "passive"))
      (node (ref "C68") (pin "2") (pinfunction "2_2") (pintype "passive"))
      (node (ref "C69") (pin "2") (pinfunction "2_2") (pintype "passive"))
      (node (ref "C70") (pin "2") (pinfunction "2_2") (pintype "passive"))
      (node (ref "C71") (pin "2") (pinfunction "2_2") (pintype "passive"))
      (node (ref "C72") (pin "2") (pinfunction "2_2") (pintype "passive"))
      (node (ref "C73") (pin "2") (pinfunction "2_2") (pintype "passive"))
      (node (ref "C74") (pin "2") (pinfunction "2_2") (pintype "passive"))
      (node (ref "C75") (pin "1") (pinfunction "1_1") (pintype "passive"))
      (node (ref "C76") (pin "1") (pinfunction "1_1") (pintype "passive"))
      (node (ref "C77") (pin "1") (pinfunction "1_1") (pintype "passive"))
      (node (ref "C78") (pin "2") (pinfunction "2_2") (pintype "passive"))
      (node (ref "C79") (pin "2") (pinfunction "2_2") (pintype "passive"))
      (node (ref "C80") (pin "2") (pinfunction "2_2") (pintype "passive"))
      (node (ref "C81") (pin "1") (pinfunction "1_1") (pintype "passive"))
      (node (ref "C82") (pin "1") (pinfunction "1_1") (pintype "passive"))
      (node (ref "C83") (pin "1") (pinfunction "1_1") (pintype "passive"))
      (node (ref "C84") (pin "2") (pinfunction "2_2") (pintype "passive"))
      (node (ref "C85") (pin "2") (pinfunction "2_2") (pintype "passive"))
      (node (ref "C86") (pin "1") (pinfunction "1_1") (pintype "passive"))
      (node (ref "H1") (pin "10") (pinfunction "10_10") (pintype "passive"))
      (node (ref "H1") (pin "13") (pinfunction "13_13") (pintype "passive"))
      (node (ref "H1") (pin "19") (pinfunction "19_19") (pintype "passive"))
      (node (ref "H1") (pin "26") (pinfunction "26_26") (pintype "passive"))
      (node (ref "H1") (pin "29") (pinfunction "29_29") (pintype "passive"))
      (node (ref "H1") (pin "33") (pinfunction "33_33") (pintype "passive"))
      (node (ref "H1") (pin "40") (pinfunction "40_40") (pintype "passive"))
      (node (ref "H1") (pin "5") (pinfunction "5_5") (pintype "passive"))
      (node (ref "JP1") (pin "2") (pinfunction "GND_2") (pintype "passive"))
      (node (ref "JP1") (pin "3") (pinfunction "GND_3") (pintype "passive"))
      (node (ref "R52") (pin "2") (pinfunction "2_2") (pintype "passive"))
      (node (ref "U3") (pin "19") (pinfunction "TEN_19") (pintype "passive"))
      (node (ref "U3") (pin "41") (pinfunction "EPAD_41") (pintype "passive"))
      (node (ref "U4") (pin "A6") (pinfunction "VSS_A6") (pintype "passive"))
      (node (ref "U4") (pin "C4") (pinfunction "VSSQ_C4") (pintype "passive"))
      (node (ref "U4") (pin "E7") (pinfunction "VSS_E7") (pintype "passive"))
      (node (ref "U4") (pin "G5") (pinfunction "VSS_G5") (pintype "passive"))
      (node (ref "U4") (pin "H10") (pinfunction "VSS_H10") (pintype "passive"))
      (node (ref "U4") (pin "J5") (pinfunction "VSS_J5") (pintype "passive"))
      (node (ref "U4") (pin "K8") (pinfunction "VSS_K8") (pintype "passive"))
      (node (ref "U4") (pin "N2") (pinfunction "VSSQ_N2") (pintype "passive"))
      (node (ref "U4") (pin "N5") (pinfunction "VSSQ_N5") (pintype "passive"))
      (node (ref "U4") (pin "P4") (pinfunction "VSSQ_P4") (pintype "passive"))
      (node (ref "U4") (pin "P6") (pinfunction "VSSQ_P6") (pintype "passive"))
      (node (ref "X1") (pin "2") (pinfunction "GND_2") (pintype "passive"))
      (node (ref "X1") (pin "4") (pinfunction "GND_4") (pintype "passive"))
    )
    (net (code "73") (name "Net-(JP1-SIG)") (class "Default")
      (node (ref "C67") (pin "2") (pinfunction "2_2") (pintype "passive"))
      (node (ref "JP1") (pin "1") (pinfunction "SIG_1") (pintype "passive"))
      (node (ref "R18") (pin "2") (pinfunction "2_2") (pintype "passive"))
    )
    (net (code "74") (name "Net-(U3-ANT)") (class "Default")
      (node (ref "C66") (pin "2") (pinfunction "2_2") (pintype "passive"))
      (node (ref "R18") (pin "1") (pinfunction "1_1") (pintype "passive"))
      (node (ref "U3") (pin "40") (pinfunction "ANT_40") (pintype "passive"))
    )
    (net (code "75") (name "Net-(U3-BT_HOST_WKUP)") (class "Default")
      (node (ref "R20") (pin "2") (pinfunction "2_2") (pintype "passive"))
      (node (ref "U3") (pin "5") (pinfunction "BT_HOST_WKUP_5") (pintype "passive"))
    )
    (net (code "76") (name "Net-(U3-BT_WKUP_HOST)") (class "Default")
      (node (ref "R19") (pin "2") (pinfunction "2_2") (pintype "passive"))
      (node (ref "U3") (pin "6") (pinfunction "BT_WKUP_HOST_6") (pintype "passive"))
    )
    (net (code "77") (name "Net-(U3-VDD12_CLK)") (class "Default")
      (node (ref "C70") (pin "1") (pinfunction "1_1") (pintype "passive"))
      (node (ref "U3") (pin "2") (pinfunction "VDD12_CLK_2") (pintype "passive"))
    )
    (net (code "78") (name "Net-(U3-VDD12_DIG)") (class "Default")
      (node (ref "C73") (pin "1") (pinfunction "1_1") (pintype "passive"))
      (node (ref "U3") (pin "21") (pinfunction "VDD12_DIG_21") (pintype "passive"))
    )
    (net (code "79") (name "Net-(U3-VDD14_DIG)") (class "Default")
      (node (ref "C74") (pin "1") (pinfunction "1_1") (pintype "passive"))
      (node (ref "C78") (pin "1") (pinfunction "1_1") (pintype "passive"))
      (node (ref "C79") (pin "1") (pinfunction "1_1") (pintype "passive"))
      (node (ref "C84") (pin "1") (pinfunction "1_1") (pintype "passive"))
      (node (ref "U3") (pin "1") (pinfunction "VDD14_RX_1") (pintype "passive"))
      (node (ref "U3") (pin "22") (pinfunction "VDD14_DIG_22") (pintype "passive"))
      (node (ref "U3") (pin "28") (pinfunction "VDD_SENSE_28") (pintype "passive"))
      (node (ref "U3") (pin "36") (pinfunction "VDD14_TX_36") (pintype "passive"))
    )
    (net (code "80") (name "Net-(U3-VDD33_PA)") (class "Default")
      (node (ref "C71") (pin "1") (pinfunction "1_1") (pintype "passive"))
      (node (ref "U3") (pin "38") (pinfunction "VDD33_PA_38") (pintype "passive"))
    )
    (net (code "81") (name "Net-(U3-VDD_RTC)") (class "Default")
      (node (ref "C72") (pin "1") (pinfunction "1_1") (pintype "passive"))
      (node (ref "U3") (pin "26") (pinfunction "VDD_RTC_26") (pintype "passive"))
    )
    (net (code "82") (name "Net-(U4-VDDI)") (class "Default")
      (node (ref "C82") (pin "2") (pinfunction "2_2") (pintype "passive"))
      (node (ref "C83") (pin "2") (pinfunction "2_2") (pintype "passive"))
      (node (ref "U4") (pin "C2") (pinfunction "VDDI_C2") (pintype "passive"))
    )
    (net (code "83") (name "Net-(U5B-PC4{slash}NAND_CE0{slash}SPI0_MISO{slash}BOOT_SEL2{slash}PC_EINT4)") (class "Default")
      (node (ref "R52") (pin "1") (pinfunction "1_1") (pintype "passive"))
      (node (ref "U5") (pin "D2") (pinfunction "PC4/NAND_CE0/SPI0_MISO/BOOT_SEL2/PC_EINT4_D2") (pintype "passive"))
    )
    (net (code "84") (name "Net-(U5B-PC5{slash}NAND_RE{slash}SDC2_CLK{slash}BOOT_SEL3{slash}PC_EINT5)") (class "Default")
      (node (ref "R12") (pin "2") (pinfunction "2_2") (pintype "passive"))
      (node (ref "U5") (pin "D3") (pinfunction "PC5/NAND_RE/SDC2_CLK/BOOT_SEL3/PC_EINT5_D3") (pintype "passive"))
    )
    (net (code "85") (name "Net-(U5B-PF2{slash}SDC0_CLK{slash}UART0_TX{slash}PF_EINT2)") (class "Default")
      (node (ref "R13") (pin "2") (pinfunction "2_2") (pintype "passive"))
      (node (ref "U5") (pin "K1") (pinfunction "PF2/SDC0_CLK/UART0_TX/PF_EINT2_K1") (pintype "passive"))
    )
    (net (code "86") (name "Net-(U5B-PG0{slash}SDC1_CLK{slash}PG_EINT0)") (class "Default")
      (node (ref "R14") (pin "2") (pinfunction "2_2") (pintype "passive"))
      (node (ref "U5") (pin "A6") (pinfunction "PG0/SDC1_CLK/PG_EINT0_A6") (pintype "passive"))
    )
    (net (code "87") (name "PS") (class "Default")
      (node (ref "H1") (pin "1") (pinfunction "1_1") (pintype "passive"))
      (node (ref "H1") (pin "3") (pinfunction "3_3") (pintype "passive"))
    )
    (net (code "88") (name "unconnected-(U3-CLKREQO-Pad18)") (class "Default")
      (node (ref "U3") (pin "18") (pinfunction "CLKREQO_18") (pintype "passive+no_connect"))
    )
    (net (code "89") (name "unconnected-(U3-NC-Pad39)") (class "Default")
      (node (ref "U3") (pin "39") (pinfunction "NC_39") (pintype "passive+no_connect"))
    )
    (net (code "90") (name "unconnected-(U3-PCM_CLK-Pad31)") (class "Default")
      (node (ref "U3") (pin "31") (pinfunction "PCM_CLK_31") (pintype "passive+no_connect"))
    )
    (net (code "91") (name "unconnected-(U3-PCM_DIN-Pad33)") (class "Default")
      (node (ref "U3") (pin "33") (pinfunction "PCM_DIN_33") (pintype "passive+no_connect"))
    )
    (net (code "92") (name "unconnected-(U3-PCM_DOUT-Pad32)") (class "Default")
      (node (ref "U3") (pin "32") (pinfunction "PCM_DOUT_32") (pintype "passive+no_connect"))
    )
    (net (code "93") (name "unconnected-(U3-PCM_SYNC-Pad34)") (class "Default")
      (node (ref "U3") (pin "34") (pinfunction "PCM_SYNC_34") (pintype "passive+no_connect"))
    )
    (net (code "94") (name "unconnected-(U3-VDD25_EF-Pad27)") (class "Default")
      (node (ref "U3") (pin "27") (pinfunction "VDD25_EF_27") (pintype "passive+no_connect"))
    )
    (net (code "95") (name "unconnected-(U3-VDD_VLX-Pad29)") (class "Default")
      (node (ref "U3") (pin "29") (pinfunction "VDD_VLX_29") (pintype "passive+no_connect"))
    )
    (net (code "96") (name "unconnected-(U4-RFU-PadG3)") (class "Default")
      (node (ref "U4") (pin "G3") (pinfunction "RFU_G3") (pintype "passive+no_connect"))
    )
    (net (code "97") (name "unconnected-(U5B-PC3{slash}NAND_CE1{slash}SPI0_CS0{slash}BOOT_SEL1{slash}PC_EINT3-PadD1)") (class "Default")
      (node (ref "U5") (pin "D1") (pinfunction "PC3/NAND_CE1/SPI0_CS0/BOOT_SEL1/PC_EINT3_D1") (pintype "passive+no_connect"))
    )
    (net (code "98") (name "unconnected-(U5B-PC7{slash}NAND_RB1{slash}SPI0_CS1{slash}PC_EINT7-PadF4)") (class "Default")
      (node (ref "U5") (pin "F4") (pinfunction "PC7/NAND_RB1/SPI0_CS1/PC_EINT7_F4") (pintype "passive+no_connect"))
    )
    (net (code "99") (name "unconnected-(U5B-PC12{slash}NAND_DQS{slash}PC_EINT12-PadG2)") (class "Default")
      (node (ref "U5") (pin "G2") (pinfunction "PC12/NAND_DQS/PC_EINT12_G2") (pintype "passive+no_connect"))
    )
    (net (code "100") (name "unconnected-(U5B-PG14{slash}H_I2S2_DIN0{slash}H_I2S2_DOUT1{slash}BIST_RESULT3{slash}AC_ADCX{slash}PG_EINT14-PadB9)") (class "Default")
      (node (ref "U5") (pin "B9") (pinfunction "PG14/H_I2S2_DIN0/H_I2S2_DOUT1/BIST_RESULT3/AC_ADCX/PG_EINT14_B9") (pintype "passive+no_connect"))
    )
    (net (code "101") (name "unconnected-(U5B-PG15{slash}UART2_TX{slash}TWI4_SCK{slash}PG_EINT15-PadA8)") (class "Default")
      (node (ref "U5") (pin "A8") (pinfunction "PG15/UART2_TX/TWI4_SCK/PG_EINT15_A8") (pintype "passive+no_connect"))
    )
    (net (code "102") (name "unconnected-(U5B-PG16{slash}UART2_RX{slash}TWI4_SDA{slash}PG_EINT16-PadB8)") (class "Default")
      (node (ref "U5") (pin "B8") (pinfunction "PG16/UART2_RX/TWI4_SDA/PG_EINT16_B8") (pintype "passive+no_connect"))
    )
    (net (code "103") (name "unconnected-(U5B-PG17{slash}UART2_RTS{slash}MCSI_SCK{slash}TWI3_SCK{slash}PG_EINT17-PadC3)") (class "Default")
      (node (ref "U5") (pin "C3") (pinfunction "PG17/UART2_RTS/MCSI_SCK/TWI3_SCK/PG_EINT17_C3") (pintype "passive+no_connect"))
    )
    (net (code "104") (name "unconnected-(U5B-PG19{slash}MCSI_MCLK{slash}PWM1{slash}PG_EINT19-PadB2)") (class "Default")
      (node (ref "U5") (pin "B2") (pinfunction "PG19/MCSI_MCLK/PWM1/PG_EINT19_B2") (pintype "passive+no_connect"))
    )
  )
)
